# botpanico_v1.net
KiCad netlist of a schematic drawn in Altium Designer
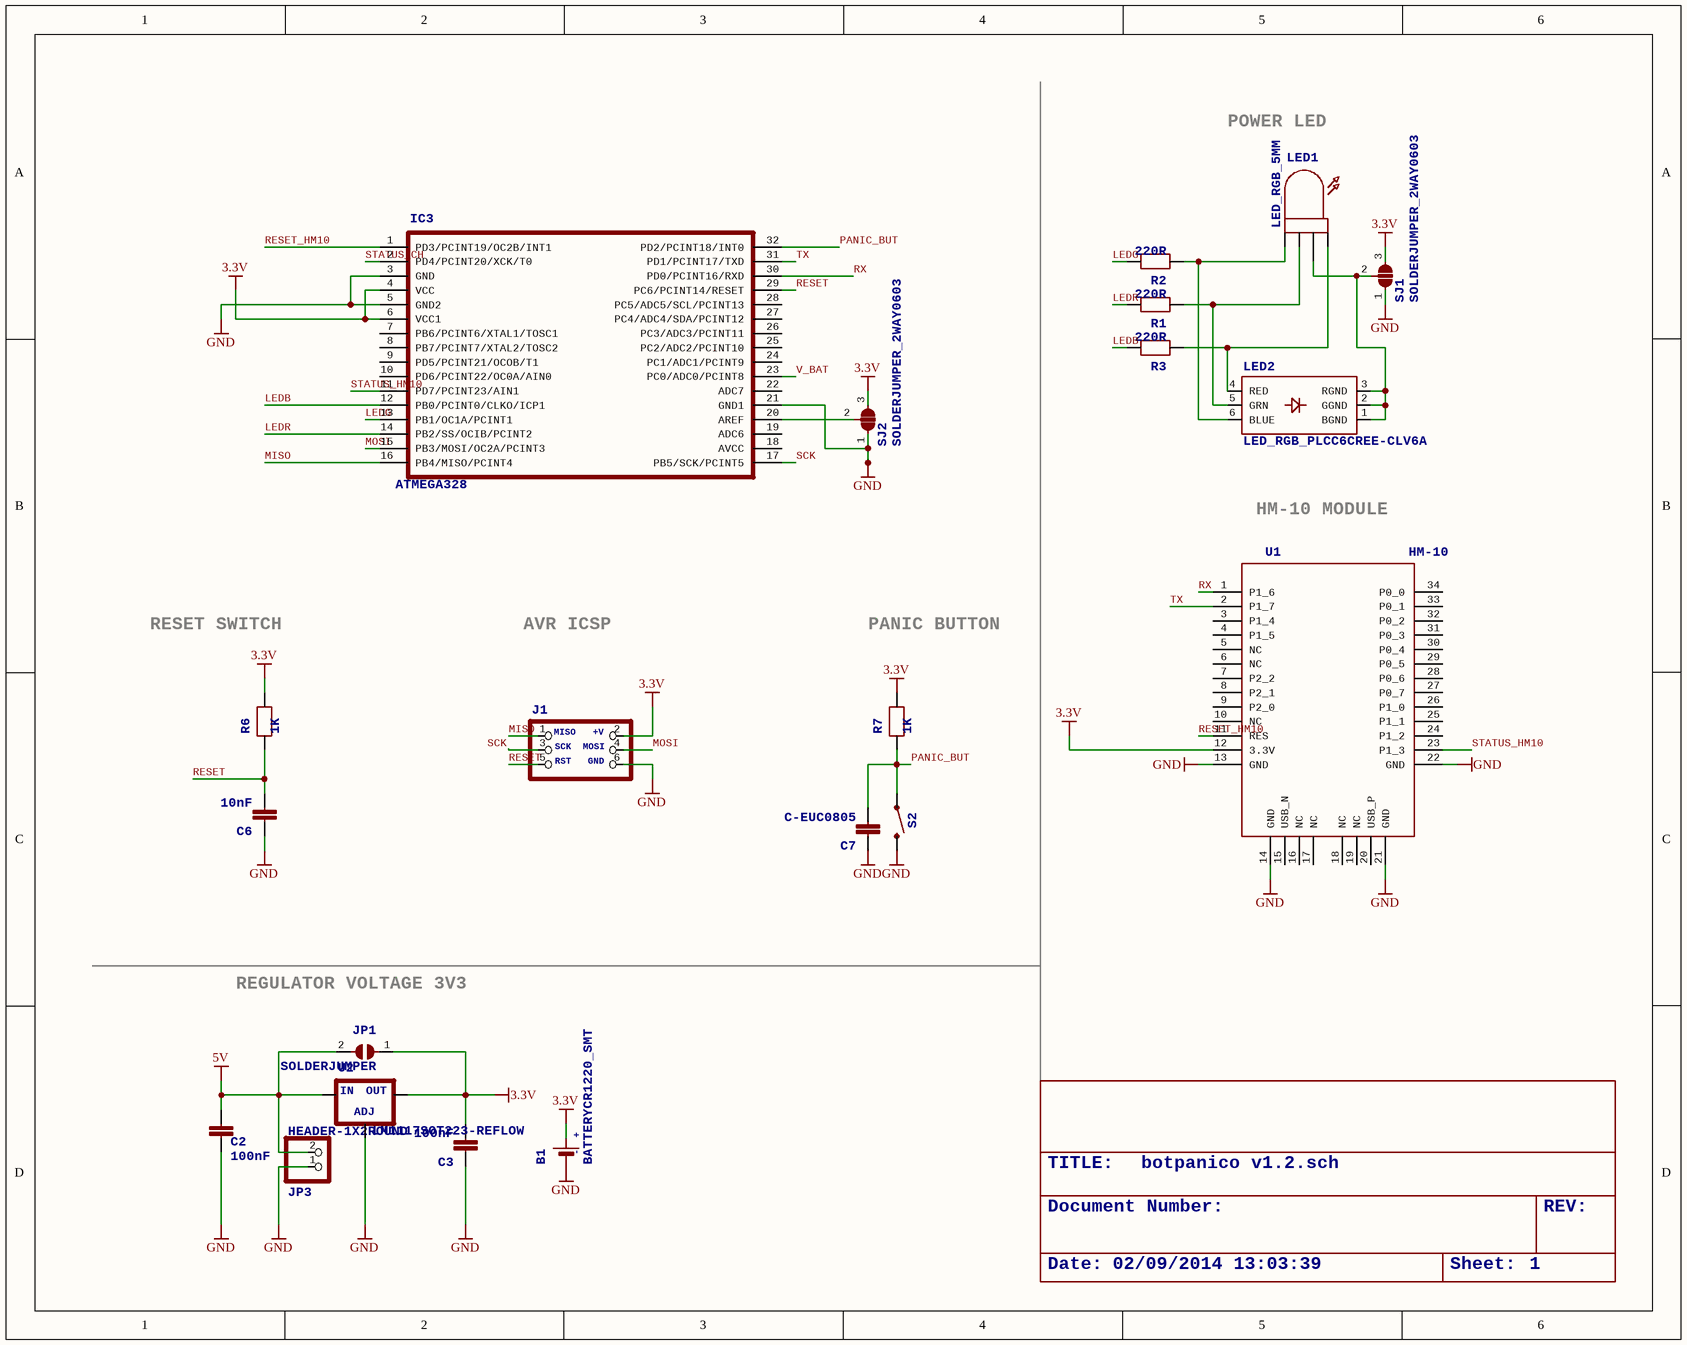
[diagram p0: botpanico v1.SchDoc]

(export (version "E")
  (design (tool "Eeschema 10.0.6"))
  (components
    (comp (ref "B1")
      (value "BATTERYCR1220_SMT")
      (footprint "CR1220")
      (description "<p>\n<ul>\n<li><b>CR1220 SMT</b> - Digikey: 3001K-ND</li>\n</ul>\n\n</p>")
      (fields (field (name "+") "+") (field (name "-") "-"))
      (libsource (lib "microbuilder") (part "BATTERYCR1220_SMT"))
    )
    (comp (ref "C2")
      (value "100nF")
      (footprint "C0805")
      (description "<B>CAPACITOR</B>, European symbol")
      (libsource (lib "") (part "C-EUC0805_1"))
    )
    (comp (ref "C3")
      (value "100nF")
      (footprint "C0805")
      (description "<B>CAPACITOR</B>, European symbol")
      (libsource (lib "rcl") (part "C-EUC0805"))
    )
    (comp (ref "C6")
      (value "10nF")
      (footprint "C0805")
      (description "<B>CAPACITOR</B>, European symbol")
      (libsource (lib "rcl") (part "C-EUC0805"))
    )
    (comp (ref "C7")
      (value "C-EUC0805")
      (footprint "C0805")
      (description "<B>CAPACITOR</B>, European symbol")
      (libsource (lib "rcl") (part "C-EUC0805"))
    )
    (comp (ref "FRAME1")
      (value "BLE112 Breakout Board v2.0")
      (description "<b>FRAME</b> A Size , 8 1/2 x 11 INCH, Landscape<p>")
      (fields
        (field (name "DATE:") "Date:")
        (field (name ">LAST_DATE_TIME") "02/09/2014 13:03:39")
        (field (name "SHEET:") "Sheet:")
        (field (name ">SHEET") "1")
        (field (name "REV:") "REV:")
        (field (name "TITLE:") "TITLE:")
        (field (name "DOCUMENT NUMBER:") "Document Number:")
        (field (name ">DRAWING_NAME") "botpanico v1.2.sch")
      )
      (libsource (lib "frames") (part "FRAME_A_L"))
    )
    (comp (ref "IC3") (value "ATMEGA328") (footprint "LQFP32") (libsource (lib "junior") (part "ATMEGA328")))
    (comp (ref "J1")
      (value "CON_HEADER_PRG_AVR_ICSP-SMD")
      (footprint "M2X3_SMD")
      (description "2x3 AVR ICSP programming header")
      (fields
        (field (name "MISO") "MISO")
        (field (name "SCK") "SCK")
        (field (name "RST") "RST")
        (field (name "+V") "+V")
        (field (name "MOSI") "MOSI")
        (field (name "GND") "GND")
      )
      (libsource (lib "dp_devices") (part "CON_HEADER_PRG_AVR_ICSP-SMD"))
    )
    (comp (ref "JP1")
      (value "SOLDERJUMPER")
      (footprint "SOLDERJUMPER_ARROW_NOPASTE")
      (libsource (lib "junior") (part "SOLDERJUMPER"))
    )
    (comp (ref "JP3")
      (value "HEADER-1X2ROUND")
      (footprint "1X02_ROUND")
      (description "<b>PIN HEADER</b>")
      (libsource (lib "junior") (part "HEADER-1X2ROUND"))
    )
    (comp (ref "LED1")
      (value "LED_RGB_5MM")
      (footprint "LEDRGB5MM")
      (libsource (lib "junior") (part "LED_RGB_5MM"))
    )
    (comp (ref "LED2")
      (value "LED_RGB_PLCC6CREE-CLV6A")
      (footprint "RGBLED_PLCC6")
      (libsource (lib "junior") (part "LED_RGB_PLCC6CREE-CLV6A"))
    )
    (comp (ref "R1") (value "220R") (footprint "0805") (libsource (lib "junior") (part "RESISTOR0805")))
    (comp (ref "R2") (value "220R") (footprint "0805") (libsource (lib "junior") (part "RESISTOR0805")))
    (comp (ref "R3") (value "220R") (footprint "0805") (libsource (lib "junior") (part "RESISTOR0805")))
    (comp (ref "R6") (value "1K") (footprint "0805") (libsource (lib "junior") (part "RESISTOR0805")))
    (comp (ref "R7") (value "1K") (footprint "0805") (libsource (lib "junior") (part "RESISTOR0805")))
    (comp (ref "S2")
      (value "SWITCH-MOMENTARY-2SMD")
      (footprint "TACTILE_SWITCH_SMD")
      (description "Various NO switches- pushbuttons, reed, etc")
      (libsource (lib "SparkFun-Electromechanical") (part "SWITCH-MOMENTARY-2SMD"))
    )
    (comp (ref "SJ1")
      (value "SOLDERJUMPER_2WAY0603")
      (footprint "SOLDERJUMPER_2WAY_OPEN_0603")
      (description "<b>2-Way Solder Jumper</b>")
      (libsource (lib "junior") (part "SOLDERJUMPER_2WAY0603"))
    )
    (comp (ref "SJ2")
      (value "SOLDERJUMPER_2WAY0603")
      (footprint "SOLDERJUMPER_2WAY_OPEN_0603")
      (description "<b>2-Way Solder Jumper</b>")
      (libsource (lib "junior") (part "SOLDERJUMPER_2WAY0603"))
    )
    (comp (ref "U1") (value "HM-10") (footprint "HM-10") (libsource (lib "junior") (part "HM-10")))
    (comp (ref "U2")
      (value "LM1117SOT223-REFLOW")
      (footprint "SOT223-R")
      (fields (field (name "ADJ") "ADJ") (field (name "IN") "IN") (field (name "OUT") "OUT"))
      (libsource (lib "junior") (part "LM1117SOT223-REFLOW"))
    )
  )
  (nets
    (net (code "1") (name "/LEDB") (class "Default")
      (node (ref "IC3") (pin "12") (pinfunction "PB0/PCINT0/CLKO/ICP1_12") (pintype "passive"))
      (node (ref "R3") (pin "2") (pinfunction "2_2") (pintype "passive"))
    )
    (net (code "2") (name "/LEDG") (class "Default")
      (node (ref "IC3") (pin "13") (pinfunction "PB1/OC1A/PCINT1_13") (pintype "passive"))
      (node (ref "R2") (pin "2") (pinfunction "2_2") (pintype "passive"))
    )
    (net (code "3") (name "/LEDR") (class "Default")
      (node (ref "IC3") (pin "14") (pinfunction "PB2/SS/OCIB/PCINT2_14") (pintype "passive"))
      (node (ref "R1") (pin "2") (pinfunction "2_2") (pintype "passive"))
    )
    (net (code "4") (name "/MISO") (class "Default")
      (node (ref "IC3") (pin "16") (pinfunction "PB4/MISO/PCINT4_16") (pintype "passive"))
      (node (ref "J1") (pin "1") (pinfunction "MISO_1") (pintype "passive"))
    )
    (net (code "5") (name "/MOSI") (class "Default")
      (node (ref "IC3") (pin "15") (pinfunction "PB3/MOSI/OC2A/PCINT3_15") (pintype "passive"))
      (node (ref "J1") (pin "4") (pinfunction "MOSI_4") (pintype "passive"))
    )
    (net (code "6") (name "/PANIC_BUT") (class "Default")
      (node (ref "C7") (pin "2") (pinfunction "2_2") (pintype "passive"))
      (node (ref "IC3") (pin "32") (pinfunction "PD2/PCINT18/INT0_32") (pintype "passive"))
      (node (ref "R7") (pin "1") (pinfunction "1_1") (pintype "passive"))
      (node (ref "S2") (pin "1") (pinfunction "1_1") (pintype "passive"))
    )
    (net (code "7") (name "/RESET") (class "Default")
      (node (ref "C6") (pin "2") (pinfunction "2_2") (pintype "passive"))
      (node (ref "IC3") (pin "29") (pinfunction "PC6/PCINT14/RESET_29") (pintype "passive"))
      (node (ref "J1") (pin "5") (pinfunction "RST_5") (pintype "passive"))
      (node (ref "R6") (pin "1") (pinfunction "1_1") (pintype "passive"))
    )
    (net (code "8") (name "/RESET_HM10") (class "Default")
      (node (ref "IC3") (pin "1") (pinfunction "PD3/PCINT19/OC2B/INT1_1") (pintype "passive"))
      (node (ref "U1") (pin "11") (pinfunction "RES_11") (pintype "passive"))
    )
    (net (code "9") (name "/RX") (class "Default")
      (node (ref "IC3") (pin "30") (pinfunction "PD0/PCINT16/RXD_30") (pintype "passive"))
      (node (ref "U1") (pin "1") (pinfunction "P1_6_1") (pintype "passive"))
    )
    (net (code "10") (name "/SCK") (class "Default")
      (node (ref "IC3") (pin "17") (pinfunction "PB5/SCK/PCINT5_17") (pintype "passive"))
    )
    (net (code "11") (name "/STATUS_CH") (class "Default")
      (node (ref "IC3") (pin "2") (pinfunction "PD4/PCINT20/XCK/T0_2") (pintype "passive"))
    )
    (net (code "12") (name "/STATUS_HM10") (class "Default")
      (node (ref "IC3") (pin "11") (pinfunction "PD7/PCINT23/AIN1_11") (pintype "passive"))
      (node (ref "U1") (pin "23") (pinfunction "P1_3_23") (pintype "passive"))
    )
    (net (code "13") (name "/TX") (class "Default")
      (node (ref "IC3") (pin "31") (pinfunction "PD1/PCINT17/TXD_31") (pintype "passive"))
      (node (ref "U1") (pin "2") (pinfunction "P1_7_2") (pintype "passive"))
    )
    (net (code "14") (name "/V_BAT") (class "Default")
      (node (ref "IC3") (pin "23") (pinfunction "PC0/ADC0/PCINT8_23") (pintype "passive"))
    )
    (net (code "15") (name "3.3V") (class "Default")
      (node (ref "B1") (pin "+$1") (pinfunction "+_+$1") (pintype "passive"))
      (node (ref "C3") (pin "2") (pinfunction "2_2") (pintype "passive"))
      (node (ref "IC3") (pin "4") (pinfunction "VCC_4") (pintype "passive"))
      (node (ref "IC3") (pin "6") (pinfunction "VCC1_6") (pintype "passive"))
      (node (ref "J1") (pin "2") (pinfunction "+V_2") (pintype "passive"))
      (node (ref "JP1") (pin "1") (pinfunction "1_1") (pintype "passive"))
      (node (ref "R6") (pin "2") (pinfunction "2_2") (pintype "passive"))
      (node (ref "R7") (pin "2") (pinfunction "2_2") (pintype "passive"))
      (node (ref "SJ1") (pin "3") (pinfunction "3_3") (pintype "passive"))
      (node (ref "SJ2") (pin "3") (pinfunction "3_3") (pintype "passive"))
      (node (ref "U1") (pin "12") (pinfunction "3.3V_12") (pintype "passive"))
      (node (ref "U2") (pin "2") (pinfunction "OUT_2") (pintype "passive"))
    )
    (net (code "16") (name "5V") (class "Default")
      (node (ref "C2") (pin "2") (pinfunction "2_2") (pintype "passive"))
      (node (ref "JP1") (pin "2") (pinfunction "2_2") (pintype "passive"))
      (node (ref "JP3") (pin "2") (pinfunction "2_2") (pintype "passive"))
      (node (ref "U2") (pin "3") (pinfunction "IN_3") (pintype "passive"))
    )
    (net (code "17") (name "GND") (class "Default")
      (node (ref "B1") (pin "-") (pinfunction "-_-") (pintype "passive"))
      (node (ref "C2") (pin "1") (pinfunction "1_1") (pintype "passive"))
      (node (ref "C3") (pin "1") (pinfunction "1_1") (pintype "passive"))
      (node (ref "C6") (pin "1") (pinfunction "1_1") (pintype "passive"))
      (node (ref "C7") (pin "1") (pinfunction "1_1") (pintype "passive"))
      (node (ref "IC3") (pin "21") (pinfunction "GND1_21") (pintype "passive"))
      (node (ref "IC3") (pin "3") (pinfunction "GND_3") (pintype "passive"))
      (node (ref "IC3") (pin "5") (pinfunction "GND2_5") (pintype "passive"))
      (node (ref "J1") (pin "6") (pinfunction "GND_6") (pintype "passive"))
      (node (ref "JP3") (pin "1") (pinfunction "1_1") (pintype "passive"))
      (node (ref "S2") (pin "3") (pinfunction "2_3") (pintype "passive"))
      (node (ref "SJ1") (pin "1") (pinfunction "1_1") (pintype "passive"))
      (node (ref "SJ2") (pin "1") (pinfunction "1_1") (pintype "passive"))
      (node (ref "U1") (pin "13") (pinfunction "GND_13") (pintype "passive"))
      (node (ref "U1") (pin "14") (pinfunction "GND_14") (pintype "passive"))
      (node (ref "U1") (pin "21") (pinfunction "GND_21") (pintype "passive"))
      (node (ref "U1") (pin "22") (pinfunction "GND_22") (pintype "passive"))
      (node (ref "U2") (pin "1") (pinfunction "ADJ_1") (pintype "passive"))
    )
    (net (code "18") (name "Net-(IC3-AREF)") (class "Default")
      (node (ref "IC3") (pin "20") (pinfunction "AREF_20") (pintype "passive"))
      (node (ref "SJ2") (pin "2") (pinfunction "2_2") (pintype "passive"))
    )
    (net (code "19") (name "Net-(LED1-B)") (class "Default")
      (node (ref "LED1") (pin "4") (pinfunction "B_4") (pintype "passive"))
      (node (ref "LED2") (pin "4") (pinfunction "RED_4") (pintype "passive"))
      (node (ref "R3") (pin "1") (pinfunction "1_1") (pintype "passive"))
    )
    (net (code "20") (name "Net-(LED1-C)") (class "Default")
      (node (ref "LED1") (pin "3") (pinfunction "C_3") (pintype "passive"))
      (node (ref "LED2") (pin "1") (pinfunction "BGND_1") (pintype "power_in"))
      (node (ref "LED2") (pin "2") (pinfunction "GGND_2") (pintype "power_in"))
      (node (ref "LED2") (pin "3") (pinfunction "RGND_3") (pintype "power_in"))
      (node (ref "SJ1") (pin "2") (pinfunction "2_2") (pintype "passive"))
    )
    (net (code "21") (name "Net-(LED1-G)") (class "Default")
      (node (ref "LED1") (pin "1") (pinfunction "G_1") (pintype "passive"))
      (node (ref "LED2") (pin "6") (pinfunction "BLUE_6") (pintype "passive"))
      (node (ref "R2") (pin "1") (pinfunction "1_1") (pintype "passive"))
    )
    (net (code "22") (name "Net-(LED1-R)") (class "Default")
      (node (ref "LED1") (pin "2") (pinfunction "R_2") (pintype "passive"))
      (node (ref "LED2") (pin "5") (pinfunction "GRN_5") (pintype "passive"))
      (node (ref "R1") (pin "1") (pinfunction "1_1") (pintype "passive"))
    )
    (net (code "23") (name "unconnected-(IC3-ADC6-Pad19)") (class "Default")
      (node (ref "IC3") (pin "19") (pinfunction "ADC6_19") (pintype "passive"))
    )
    (net (code "24") (name "unconnected-(IC3-ADC7-Pad22)") (class "Default")
      (node (ref "IC3") (pin "22") (pinfunction "ADC7_22") (pintype "passive"))
    )
    (net (code "25") (name "unconnected-(IC3-AVCC-Pad18)") (class "Default")
      (node (ref "IC3") (pin "18") (pinfunction "AVCC_18") (pintype "passive"))
    )
    (net (code "26") (name "unconnected-(IC3-PB6{slash}PCINT6{slash}XTAL1{slash}TOSC1-Pad7)") (class "Default")
      (node (ref "IC3") (pin "7") (pinfunction "PB6/PCINT6/XTAL1/TOSC1_7") (pintype "passive"))
    )
    (net (code "27") (name "unconnected-(IC3-PB7{slash}PCINT7{slash}XTAL2{slash}TOSC2-Pad8)") (class "Default")
      (node (ref "IC3") (pin "8") (pinfunction "PB7/PCINT7/XTAL2/TOSC2_8") (pintype "passive"))
    )
    (net (code "28") (name "unconnected-(IC3-PC1{slash}ADC1{slash}PCINT9-Pad24)") (class "Default")
      (node (ref "IC3") (pin "24") (pinfunction "PC1/ADC1/PCINT9_24") (pintype "passive"))
    )
    (net (code "29") (name "unconnected-(IC3-PC2{slash}ADC2{slash}PCINT10-Pad25)") (class "Default")
      (node (ref "IC3") (pin "25") (pinfunction "PC2/ADC2/PCINT10_25") (pintype "passive"))
    )
    (net (code "30") (name "unconnected-(IC3-PC3{slash}ADC3{slash}PCINT11-Pad26)") (class "Default")
      (node (ref "IC3") (pin "26") (pinfunction "PC3/ADC3/PCINT11_26") (pintype "passive"))
    )
    (net (code "31") (name "unconnected-(IC3-PC4{slash}ADC4{slash}SDA{slash}PCINT12-Pad27)") (class "Default")
      (node (ref "IC3") (pin "27") (pinfunction "PC4/ADC4/SDA/PCINT12_27") (pintype "passive"))
    )
    (net (code "32") (name "unconnected-(IC3-PC5{slash}ADC5{slash}SCL{slash}PCINT13-Pad28)") (class "Default")
      (node (ref "IC3") (pin "28") (pinfunction "PC5/ADC5/SCL/PCINT13_28") (pintype "passive"))
    )
    (net (code "33") (name "unconnected-(IC3-PD5{slash}PCINT21{slash}OCOB{slash}T1-Pad9)") (class "Default")
      (node (ref "IC3") (pin "9") (pinfunction "PD5/PCINT21/OCOB/T1_9") (pintype "passive"))
    )
    (net (code "34") (name "unconnected-(IC3-PD6{slash}PCINT22{slash}OC0A{slash}AIN0-Pad10)") (class "Default")
      (node (ref "IC3") (pin "10") (pinfunction "PD6/PCINT22/OC0A/AIN0_10") (pintype "passive"))
    )
    (net (code "35") (name "unconnected-(J1-SCK-Pad3)") (class "Default")
      (node (ref "J1") (pin "3") (pinfunction "SCK_3") (pintype "passive"))
    )
    (net (code "36") (name "unconnected-(U1-NC-Pad5)") (class "Default")
      (node (ref "U1") (pin "5") (pinfunction "NC_5") (pintype "passive"))
    )
    (net (code "37") (name "unconnected-(U1-NC-Pad6)") (class "Default")
      (node (ref "U1") (pin "6") (pinfunction "NC_6") (pintype "passive"))
    )
    (net (code "38") (name "unconnected-(U1-NC-Pad10)") (class "Default")
      (node (ref "U1") (pin "10") (pinfunction "NC_10") (pintype "passive"))
    )
    (net (code "39") (name "unconnected-(U1-NC-Pad16)") (class "Default")
      (node (ref "U1") (pin "16") (pinfunction "NC_16") (pintype "passive"))
    )
    (net (code "40") (name "unconnected-(U1-NC-Pad17)") (class "Default")
      (node (ref "U1") (pin "17") (pinfunction "NC_17") (pintype "passive"))
    )
    (net (code "41") (name "unconnected-(U1-NC-Pad18)") (class "Default")
      (node (ref "U1") (pin "18") (pinfunction "NC_18") (pintype "passive"))
    )
    (net (code "42") (name "unconnected-(U1-NC-Pad19)") (class "Default")
      (node (ref "U1") (pin "19") (pinfunction "NC_19") (pintype "passive"))
    )
    (net (code "43") (name "unconnected-(U1-P0_0-Pad34)") (class "Default")
      (node (ref "U1") (pin "34") (pinfunction "P0_0_34") (pintype "passive"))
    )
    (net (code "44") (name "unconnected-(U1-P0_1-Pad33)") (class "Default")
      (node (ref "U1") (pin "33") (pinfunction "P0_1_33") (pintype "passive"))
    )
    (net (code "45") (name "unconnected-(U1-P0_2-Pad32)") (class "Default")
      (node (ref "U1") (pin "32") (pinfunction "P0_2_32") (pintype "passive"))
    )
    (net (code "46") (name "unconnected-(U1-P0_3-Pad31)") (class "Default")
      (node (ref "U1") (pin "31") (pinfunction "P0_3_31") (pintype "passive"))
    )
    (net (code "47") (name "unconnected-(U1-P0_4-Pad30)") (class "Default")
      (node (ref "U1") (pin "30") (pinfunction "P0_4_30") (pintype "passive"))
    )
    (net (code "48") (name "unconnected-(U1-P0_5-Pad29)") (class "Default")
      (node (ref "U1") (pin "29") (pinfunction "P0_5_29") (pintype "passive"))
    )
    (net (code "49") (name "unconnected-(U1-P0_6-Pad28)") (class "Default")
      (node (ref "U1") (pin "28") (pinfunction "P0_6_28") (pintype "passive"))
    )
    (net (code "50") (name "unconnected-(U1-P0_7-Pad27)") (class "Default")
      (node (ref "U1") (pin "27") (pinfunction "P0_7_27") (pintype "passive"))
    )
    (net (code "51") (name "unconnected-(U1-P1_0-Pad26)") (class "Default")
      (node (ref "U1") (pin "26") (pinfunction "P1_0_26") (pintype "passive"))
    )
    (net (code "52") (name "unconnected-(U1-P1_1-Pad25)") (class "Default")
      (node (ref "U1") (pin "25") (pinfunction "P1_1_25") (pintype "passive"))
    )
    (net (code "53") (name "unconnected-(U1-P1_2-Pad24)") (class "Default")
      (node (ref "U1") (pin "24") (pinfunction "P1_2_24") (pintype "passive"))
    )
    (net (code "54") (name "unconnected-(U1-P1_4-Pad3)") (class "Default")
      (node (ref "U1") (pin "3") (pinfunction "P1_4_3") (pintype "passive"))
    )
    (net (code "55") (name "unconnected-(U1-P1_5-Pad4)") (class "Default")
      (node (ref "U1") (pin "4") (pinfunction "P1_5_4") (pintype "passive"))
    )
    (net (code "56") (name "unconnected-(U1-P2_0-Pad9)") (class "Default")
      (node (ref "U1") (pin "9") (pinfunction "P2_0_9") (pintype "passive"))
    )
    (net (code "57") (name "unconnected-(U1-P2_1-Pad8)") (class "Default")
      (node (ref "U1") (pin "8") (pinfunction "P2_1_8") (pintype "passive"))
    )
    (net (code "58") (name "unconnected-(U1-P2_2-Pad7)") (class "Default")
      (node (ref "U1") (pin "7") (pinfunction "P2_2_7") (pintype "passive"))
    )
    (net (code "59") (name "unconnected-(U1-USB_N-Pad15)") (class "Default")
      (node (ref "U1") (pin "15") (pinfunction "USB_N_15") (pintype "passive"))
    )
    (net (code "60") (name "unconnected-(U1-USB_P-Pad20)") (class "Default")
      (node (ref "U1") (pin "20") (pinfunction "USB_P_20") (pintype "passive"))
    )
  )
)
